# motherboard_v3.net
KiCad netlist of a schematic drawn in EAGLE
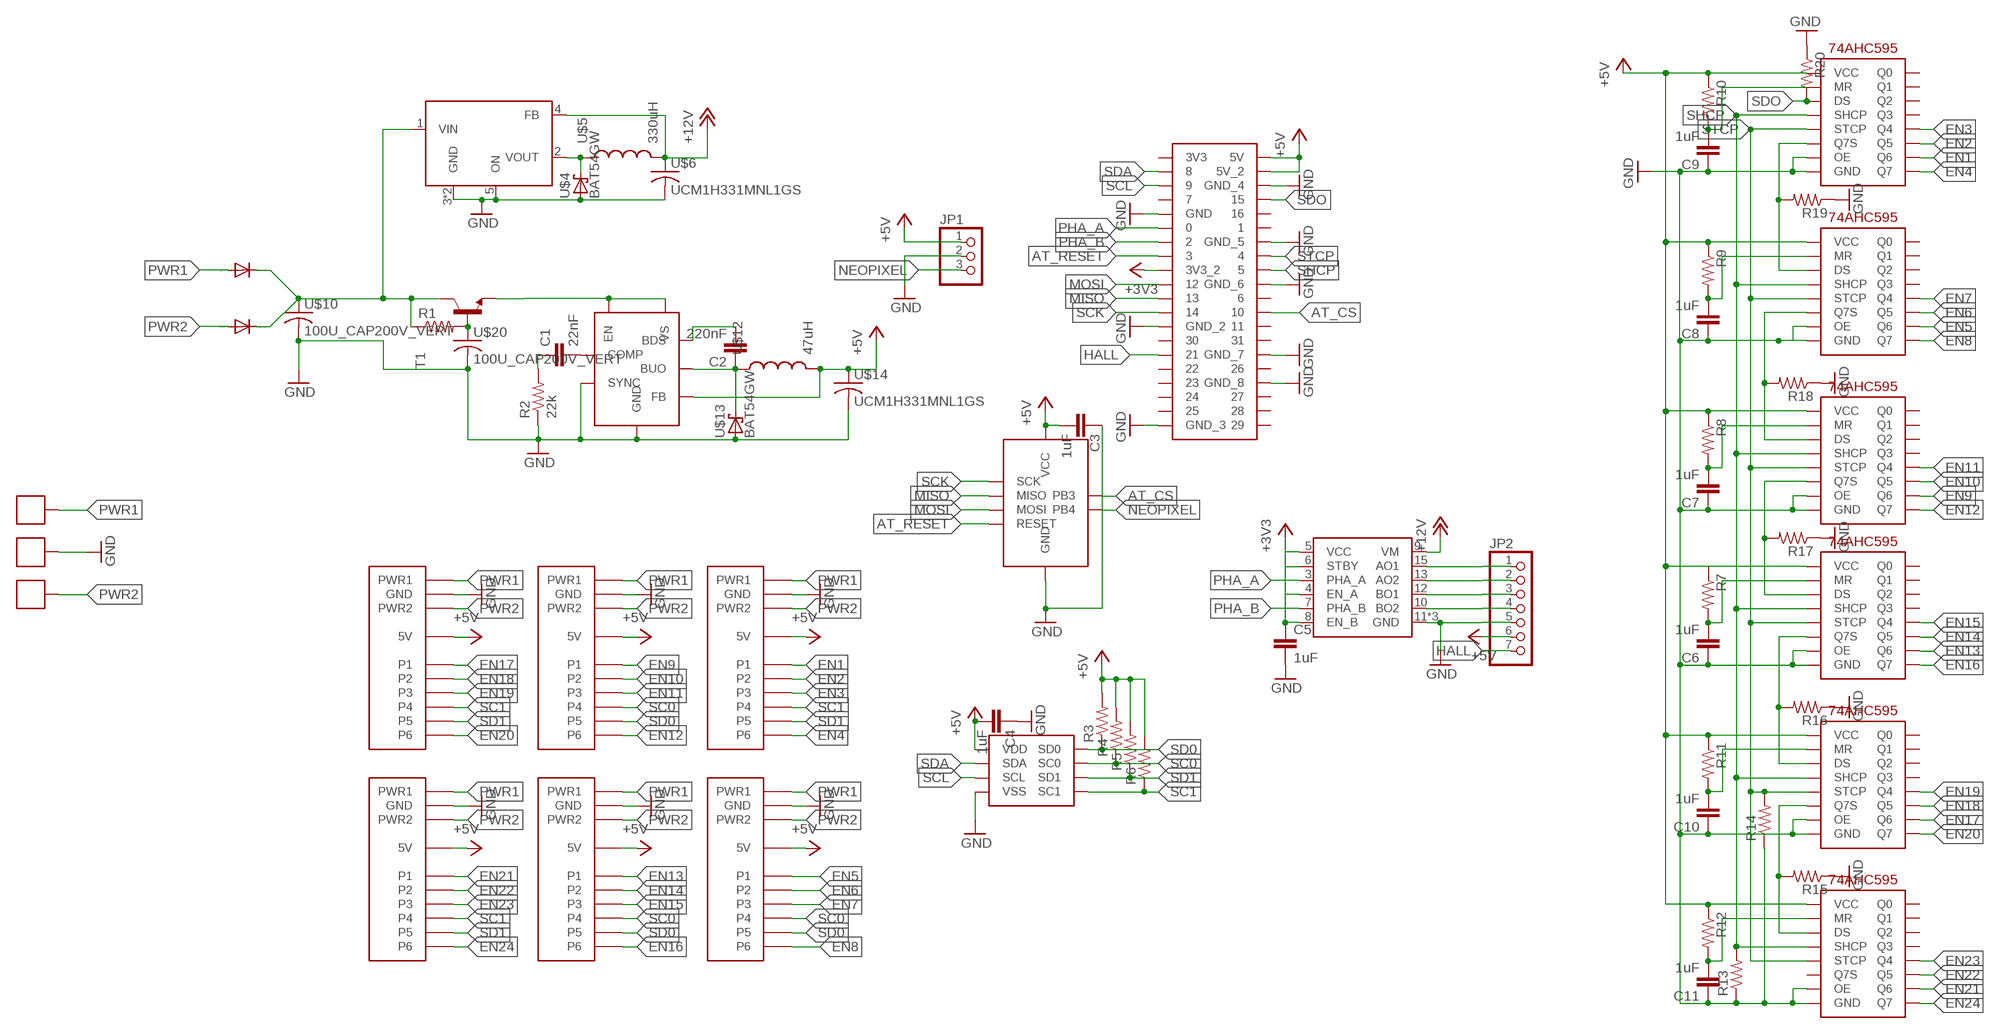
[diagram p0: schematic, sheet 1]

(export (version "E")
  (design (tool "Eeschema 10.0.6"))
  (components
    (comp (ref "B1")
      (value "PCIE_SOCKET")
      (footprint "eagle-import:PCIE_SOCKET")
      (libsource (lib "eagle-import") (part "PCIE_SOCKET"))
    )
    (comp (ref "B2")
      (value "PCIE_SOCKET")
      (footprint "eagle-import:PCIE_SOCKET")
      (libsource (lib "eagle-import") (part "PCIE_SOCKET"))
    )
    (comp (ref "B3")
      (value "PCIE_SOCKET")
      (footprint "eagle-import:PCIE_SOCKET")
      (libsource (lib "eagle-import") (part "PCIE_SOCKET"))
    )
    (comp (ref "B4")
      (value "PCIE_SOCKET")
      (footprint "eagle-import:PCIE_SOCKET")
      (libsource (lib "eagle-import") (part "PCIE_SOCKET"))
    )
    (comp (ref "B5")
      (value "PCIE_SOCKET")
      (footprint "eagle-import:PCIE_SOCKET")
      (libsource (lib "eagle-import") (part "PCIE_SOCKET"))
    )
    (comp (ref "B6")
      (value "PCIE_SOCKET")
      (footprint "eagle-import:PCIE_SOCKET")
      (libsource (lib "eagle-import") (part "PCIE_SOCKET"))
    )
    (comp (ref "C1")
      (value "22nF")
      (footprint "eagle-import:C0805")
      (libsource (lib "eagle-import") (part "C-EUC0805"))
    )
    (comp (ref "C2")
      (value "220nF")
      (footprint "eagle-import:C0805")
      (libsource (lib "eagle-import") (part "C-EUC0805"))
    )
    (comp (ref "C3")
      (value "1uF")
      (footprint "eagle-import:C0805")
      (libsource (lib "eagle-import") (part "C-EUC0805"))
    )
    (comp (ref "C4")
      (value "1uF")
      (footprint "eagle-import:C0805")
      (libsource (lib "eagle-import") (part "C-EUC0805"))
    )
    (comp (ref "C5")
      (value "1uF")
      (footprint "eagle-import:C0805")
      (libsource (lib "eagle-import") (part "C-EUC0805"))
    )
    (comp (ref "C6")
      (value "1uF")
      (footprint "eagle-import:C0805")
      (libsource (lib "eagle-import") (part "C-EUC0805"))
    )
    (comp (ref "C7")
      (value "1uF")
      (footprint "eagle-import:C0805")
      (libsource (lib "eagle-import") (part "C-EUC0805"))
    )
    (comp (ref "C8")
      (value "1uF")
      (footprint "eagle-import:C0805")
      (libsource (lib "eagle-import") (part "C-EUC0805"))
    )
    (comp (ref "C9")
      (value "1uF")
      (footprint "eagle-import:C0805")
      (libsource (lib "eagle-import") (part "C-EUC0805"))
    )
    (comp (ref "C10")
      (value "1uF")
      (footprint "eagle-import:C0805")
      (libsource (lib "eagle-import") (part "C-EUC0805"))
    )
    (comp (ref "C11")
      (value "1uF")
      (footprint "eagle-import:C0805")
      (libsource (lib "eagle-import") (part "C-EUC0805"))
    )
    (comp (ref "JP1")
      (value "PINHD-1X3")
      (footprint "eagle-import:1X03")
      (libsource (lib "eagle-import") (part "PINHD-1X3"))
    )
    (comp (ref "JP2")
      (value "PINHD-1X7")
      (footprint "eagle-import:1X07")
      (libsource (lib "eagle-import") (part "PINHD-1X7"))
    )
    (comp (ref "R1")
      (value "R-US_R1206")
      (footprint "eagle-import:R1206")
      (libsource (lib "eagle-import") (part "R-US_R1206"))
    )
    (comp (ref "R2")
      (value "22k")
      (footprint "eagle-import:R1206")
      (libsource (lib "eagle-import") (part "R-US_R1206"))
    )
    (comp (ref "R3")
      (value "R-US_R0805")
      (footprint "eagle-import:R0805")
      (libsource (lib "eagle-import") (part "R-US_R0805"))
    )
    (comp (ref "R4")
      (value "R-US_R0805")
      (footprint "eagle-import:R0805")
      (libsource (lib "eagle-import") (part "R-US_R0805"))
    )
    (comp (ref "R5")
      (value "R-US_R0805")
      (footprint "eagle-import:R0805")
      (libsource (lib "eagle-import") (part "R-US_R0805"))
    )
    (comp (ref "R6")
      (value "R-US_R0805")
      (footprint "eagle-import:R0805")
      (libsource (lib "eagle-import") (part "R-US_R0805"))
    )
    (comp (ref "R7")
      (value "R-US_R0805")
      (footprint "eagle-import:R0805")
      (libsource (lib "eagle-import") (part "R-US_R0805"))
    )
    (comp (ref "R8")
      (value "R-US_R0805")
      (footprint "eagle-import:R0805")
      (libsource (lib "eagle-import") (part "R-US_R0805"))
    )
    (comp (ref "R9")
      (value "R-US_R0805")
      (footprint "eagle-import:R0805")
      (libsource (lib "eagle-import") (part "R-US_R0805"))
    )
    (comp (ref "R10")
      (value "R-US_R0805")
      (footprint "eagle-import:R0805")
      (libsource (lib "eagle-import") (part "R-US_R0805"))
    )
    (comp (ref "R11")
      (value "R-US_R0805")
      (footprint "eagle-import:R0805")
      (libsource (lib "eagle-import") (part "R-US_R0805"))
    )
    (comp (ref "R12")
      (value "R-US_R0805")
      (footprint "eagle-import:R0805")
      (libsource (lib "eagle-import") (part "R-US_R0805"))
    )
    (comp (ref "R13")
      (value "R-US_R0805")
      (footprint "eagle-import:R0805")
      (libsource (lib "eagle-import") (part "R-US_R0805"))
    )
    (comp (ref "R14")
      (value "R-US_R0805")
      (footprint "eagle-import:R0805")
      (libsource (lib "eagle-import") (part "R-US_R0805"))
    )
    (comp (ref "R15")
      (value "R-US_R0805")
      (footprint "eagle-import:R0805")
      (libsource (lib "eagle-import") (part "R-US_R0805"))
    )
    (comp (ref "R16")
      (value "R-US_R0805")
      (footprint "eagle-import:R0805")
      (libsource (lib "eagle-import") (part "R-US_R0805"))
    )
    (comp (ref "R17")
      (value "R-US_R0805")
      (footprint "eagle-import:R0805")
      (libsource (lib "eagle-import") (part "R-US_R0805"))
    )
    (comp (ref "R18")
      (value "R-US_R0805")
      (footprint "eagle-import:R0805")
      (libsource (lib "eagle-import") (part "R-US_R0805"))
    )
    (comp (ref "R19")
      (value "R-US_R0805")
      (footprint "eagle-import:R0805")
      (libsource (lib "eagle-import") (part "R-US_R0805"))
    )
    (comp (ref "R20")
      (value "R-US_R0805")
      (footprint "eagle-import:R0805")
      (libsource (lib "eagle-import") (part "R-US_R0805"))
    )
    (comp (ref "T1")
      (value "-NPN-SOT23-EBC")
      (footprint "eagle-import:SOT23-EBC")
      (libsource (lib "eagle-import") (part "-NPN-SOT23-EBC"))
    )
    (comp (ref "U$1")
      (value "RPI_SOCKET")
      (footprint "eagle-import:40PIN_SOCKET")
      (libsource (lib "eagle-import") (part "RPI_SOCKET"))
    )
    (comp (ref "U$2")
      (value "TC78H620FNG")
      (footprint "eagle-import:SSOP16")
      (libsource (lib "eagle-import") (part "TC78H620FNG"))
    )
    (comp (ref "U$3")
      (value "TL2575HV-12IKTTR")
      (footprint "eagle-import:TO170P1524X483-6")
      (libsource (lib "eagle-import") (part "TL2575HV-12IKTTR"))
    )
    (comp (ref "U$4")
      (value "BAT54GW")
      (footprint "eagle-import:SOD3616X130")
      (libsource (lib "eagle-import") (part "BAT54GW"))
    )
    (comp (ref "U$5")
      (value "330uH")
      (footprint "eagle-import:SRN8040TA")
      (libsource (lib "eagle-import") (part "SRN8040TA"))
    )
    (comp (ref "U$6")
      (value "UCM1H331MNL1GS")
      (footprint "eagle-import:CAPAE1030X1050")
      (libsource (lib "eagle-import") (part "UCM1H331MNL1GS"))
    )
    (comp (ref "U$7")
      (value "74HC595_QFN")
      (footprint "eagle-import:QFN50P250X350X100-16")
      (libsource (lib "eagle-import") (part "74HC595_QFN"))
    )
    (comp (ref "U$8")
      (value "BAS16GW")
      (footprint "eagle-import:SOD3616X130")
      (libsource (lib "eagle-import") (part "BAS16GW"))
    )
    (comp (ref "U$9")
      (value "BAS16GW")
      (footprint "eagle-import:SOD3616X130")
      (libsource (lib "eagle-import") (part "BAS16GW"))
    )
    (comp (ref "U$10")
      (value "100U_CAP200V_VERT")
      (footprint "eagle-import:VERT_CAP")
      (libsource (lib "eagle-import") (part "100U_CAP200V_VERT"))
    )
    (comp (ref "U$11")
      (value "ATTINY85")
      (footprint "eagle-import:SOIC127P599X175-8")
      (libsource (lib "eagle-import") (part "ATTINY85"))
    )
    (comp (ref "U$12")
      (value "47uH")
      (footprint "eagle-import:SRN8040TA")
      (libsource (lib "eagle-import") (part "SRN8040TA"))
    )
    (comp (ref "U$13")
      (value "BAT54GW")
      (footprint "eagle-import:SOD3616X130")
      (libsource (lib "eagle-import") (part "BAT54GW"))
    )
    (comp (ref "U$14")
      (value "UCM1H331MNL1GS")
      (footprint "eagle-import:CAPAE1030X1050")
      (libsource (lib "eagle-import") (part "UCM1H331MNL1GS"))
    )
    (comp (ref "U$17")
      (value "1935310")
      (footprint "eagle-import:1935310")
      (libsource (lib "eagle-import") (part "1935310"))
    )
    (comp (ref "U$18")
      (value "1935310")
      (footprint "eagle-import:1935310")
      (libsource (lib "eagle-import") (part "1935310"))
    )
    (comp (ref "U$19")
      (value "1935310")
      (footprint "eagle-import:1935310")
      (libsource (lib "eagle-import") (part "1935310"))
    )
    (comp (ref "U$20")
      (value "100U_CAP200V_VERT")
      (footprint "eagle-import:VERT_CAP")
      (libsource (lib "eagle-import") (part "100U_CAP200V_VERT"))
    )
    (comp (ref "U$21")
      (value "PCA9540BDP")
      (footprint "eagle-import:TSSOP8")
      (libsource (lib "eagle-import") (part "PCA9540BDP"))
    )
    (comp (ref "U$22")
      (value "74HC595_QFN")
      (footprint "eagle-import:QFN50P250X350X100-16")
      (libsource (lib "eagle-import") (part "74HC595_QFN"))
    )
    (comp (ref "U$23")
      (value "74HC595_QFN")
      (footprint "eagle-import:QFN50P250X350X100-16")
      (libsource (lib "eagle-import") (part "74HC595_QFN"))
    )
    (comp (ref "U$24")
      (value "74HC595_QFN")
      (footprint "eagle-import:QFN50P250X350X100-16")
      (libsource (lib "eagle-import") (part "74HC595_QFN"))
    )
    (comp (ref "U$25")
      (value "74HC595_QFN")
      (footprint "eagle-import:QFN50P250X350X100-16")
      (libsource (lib "eagle-import") (part "74HC595_QFN"))
    )
    (comp (ref "U$26")
      (value "74HC595_QFN")
      (footprint "eagle-import:QFN50P250X350X100-16")
      (libsource (lib "eagle-import") (part "74HC595_QFN"))
    )
    (comp (ref "U1")
      (value "IFX91041EJV50XUMA1")
      (footprint "eagle-import:SOIC127P600X170-8")
      (libsource (lib "eagle-import") (part "IFX91041EJV50XUMA1"))
    )
  )
  (nets
    (net (code "1") (name "+3V3") (class "Default")
      (node (ref "C5") (pin "1") (pinfunction "1_1") (pintype "passive"))
      (node (ref "U$1") (pin "P17") (pinfunction "3V3_2_P17") (pintype "bidirectional"))
      (node (ref "U$2") (pin "4") (pinfunction "EN_A_4") (pintype "bidirectional"))
      (node (ref "U$2") (pin "5") (pinfunction "VCC_5") (pintype "bidirectional"))
      (node (ref "U$2") (pin "6") (pinfunction "STBY_6") (pintype "bidirectional"))
      (node (ref "U$2") (pin "8") (pinfunction "EN_B_8") (pintype "bidirectional"))
    )
    (net (code "2") (name "+5V") (class "Default")
      (node (ref "B1") (pin "5V_1") (pinfunction "5V_5V_1") (pintype "passive"))
      (node (ref "B1") (pin "5V_2") (pinfunction "5V_5V_2") (pintype "passive"))
      (node (ref "B2") (pin "5V_1") (pinfunction "5V_5V_1") (pintype "passive"))
      (node (ref "B2") (pin "5V_2") (pinfunction "5V_5V_2") (pintype "passive"))
      (node (ref "B3") (pin "5V_1") (pinfunction "5V_5V_1") (pintype "passive"))
      (node (ref "B3") (pin "5V_2") (pinfunction "5V_5V_2") (pintype "passive"))
      (node (ref "B4") (pin "5V_1") (pinfunction "5V_5V_1") (pintype "passive"))
      (node (ref "B4") (pin "5V_2") (pinfunction "5V_5V_2") (pintype "passive"))
      (node (ref "B5") (pin "5V_1") (pinfunction "5V_5V_1") (pintype "passive"))
      (node (ref "B5") (pin "5V_2") (pinfunction "5V_5V_2") (pintype "passive"))
      (node (ref "B6") (pin "5V_1") (pinfunction "5V_5V_1") (pintype "passive"))
      (node (ref "B6") (pin "5V_2") (pinfunction "5V_5V_2") (pintype "passive"))
      (node (ref "C3") (pin "2") (pinfunction "2_2") (pintype "passive"))
      (node (ref "C4") (pin "2") (pinfunction "2_2") (pintype "passive"))
      (node (ref "JP1") (pin "1") (pinfunction "1_1") (pintype "passive"))
      (node (ref "JP2") (pin "6") (pinfunction "6_6") (pintype "passive"))
      (node (ref "R10") (pin "1") (pinfunction "1_1") (pintype "passive"))
      (node (ref "R11") (pin "1") (pinfunction "1_1") (pintype "passive"))
      (node (ref "R12") (pin "1") (pinfunction "1_1") (pintype "passive"))
      (node (ref "R3") (pin "2") (pinfunction "2_2") (pintype "passive"))
      (node (ref "R4") (pin "2") (pinfunction "2_2") (pintype "passive"))
      (node (ref "R5") (pin "2") (pinfunction "2_2") (pintype "passive"))
      (node (ref "R6") (pin "2") (pinfunction "2_2") (pintype "passive"))
      (node (ref "R7") (pin "1") (pinfunction "1_1") (pintype "passive"))
      (node (ref "R8") (pin "1") (pinfunction "1_1") (pintype "passive"))
      (node (ref "R9") (pin "1") (pinfunction "1_1") (pintype "passive"))
      (node (ref "U$1") (pin "P2") (pinfunction "5V_P2") (pintype "bidirectional"))
      (node (ref "U$1") (pin "P4") (pinfunction "5V_2_P4") (pintype "bidirectional"))
      (node (ref "U$11") (pin "8") (pinfunction "VCC_8") (pintype "bidirectional"))
      (node (ref "U$12") (pin "P$2") (pinfunction "2_P$2") (pintype "passive"))
      (node (ref "U$14") (pin "1") (pinfunction "1_1") (pintype "passive"))
      (node (ref "U$21") (pin "3") (pinfunction "VDD_3") (pintype "bidirectional"))
      (node (ref "U$22") (pin "P16") (pinfunction "VCC_P16") (pintype "bidirectional"))
      (node (ref "U$23") (pin "P16") (pinfunction "VCC_P16") (pintype "bidirectional"))
      (node (ref "U$24") (pin "P16") (pinfunction "VCC_P16") (pintype "bidirectional"))
      (node (ref "U$25") (pin "P16") (pinfunction "VCC_P16") (pintype "bidirectional"))
      (node (ref "U$26") (pin "P16") (pinfunction "VCC_P16") (pintype "bidirectional"))
      (node (ref "U$7") (pin "P16") (pinfunction "VCC_P16") (pintype "bidirectional"))
      (node (ref "U1") (pin "4") (pinfunction "FB_4") (pintype "bidirectional"))
    )
    (net (code "3") (name "+12V") (class "Default")
      (node (ref "U$2") (pin "9") (pinfunction "VM_9") (pintype "bidirectional"))
      (node (ref "U$3") (pin "4") (pinfunction "FB_4") (pintype "bidirectional"))
      (node (ref "U$5") (pin "P$2") (pinfunction "2_P$2") (pintype "passive"))
      (node (ref "U$6") (pin "1") (pinfunction "1_1") (pintype "passive"))
    )
    (net (code "4") (name "AT_CS") (class "Default")
      (node (ref "U$1") (pin "P24") (pinfunction "10_P24") (pintype "bidirectional"))
      (node (ref "U$11") (pin "2") (pinfunction "PB3_2") (pintype "bidirectional"))
    )
    (net (code "5") (name "AT_RESET") (class "Default")
      (node (ref "U$1") (pin "P15") (pinfunction "3_P15") (pintype "bidirectional"))
      (node (ref "U$11") (pin "1") (pinfunction "RESET_1") (pintype "bidirectional"))
    )
    (net (code "6") (name "EN1") (class "Default")
      (node (ref "B1") (pin "P1") (pinfunction "P1_P1") (pintype "bidirectional"))
      (node (ref "U$7") (pin "P6") (pinfunction "Q6_P6") (pintype "bidirectional"))
    )
    (net (code "7") (name "EN2") (class "Default")
      (node (ref "B1") (pin "P2") (pinfunction "P2_P2") (pintype "bidirectional"))
      (node (ref "U$7") (pin "P5") (pinfunction "Q5_P5") (pintype "bidirectional"))
    )
    (net (code "8") (name "EN3") (class "Default")
      (node (ref "B1") (pin "P3") (pinfunction "P3_P3") (pintype "bidirectional"))
      (node (ref "U$7") (pin "P4") (pinfunction "Q4_P4") (pintype "bidirectional"))
    )
    (net (code "9") (name "EN4") (class "Default")
      (node (ref "B1") (pin "P6") (pinfunction "P6_P6") (pintype "bidirectional"))
      (node (ref "U$7") (pin "P7") (pinfunction "Q7_P7") (pintype "bidirectional"))
    )
    (net (code "10") (name "EN5") (class "Default")
      (node (ref "B2") (pin "P1") (pinfunction "P1_P1") (pintype "bidirectional"))
      (node (ref "U$22") (pin "P6") (pinfunction "Q6_P6") (pintype "bidirectional"))
    )
    (net (code "11") (name "EN6") (class "Default")
      (node (ref "B2") (pin "P2") (pinfunction "P2_P2") (pintype "bidirectional"))
      (node (ref "U$22") (pin "P5") (pinfunction "Q5_P5") (pintype "bidirectional"))
    )
    (net (code "12") (name "EN7") (class "Default")
      (node (ref "B2") (pin "P3") (pinfunction "P3_P3") (pintype "bidirectional"))
      (node (ref "U$22") (pin "P4") (pinfunction "Q4_P4") (pintype "bidirectional"))
    )
    (net (code "13") (name "EN8") (class "Default")
      (node (ref "B2") (pin "P6") (pinfunction "P6_P6") (pintype "bidirectional"))
      (node (ref "U$22") (pin "P7") (pinfunction "Q7_P7") (pintype "bidirectional"))
    )
    (net (code "14") (name "EN9") (class "Default")
      (node (ref "B3") (pin "P1") (pinfunction "P1_P1") (pintype "bidirectional"))
      (node (ref "U$23") (pin "P6") (pinfunction "Q6_P6") (pintype "bidirectional"))
    )
    (net (code "15") (name "EN10") (class "Default")
      (node (ref "B3") (pin "P2") (pinfunction "P2_P2") (pintype "bidirectional"))
      (node (ref "U$23") (pin "P5") (pinfunction "Q5_P5") (pintype "bidirectional"))
    )
    (net (code "16") (name "EN11") (class "Default")
      (node (ref "B3") (pin "P3") (pinfunction "P3_P3") (pintype "bidirectional"))
      (node (ref "U$23") (pin "P4") (pinfunction "Q4_P4") (pintype "bidirectional"))
    )
    (net (code "17") (name "EN12") (class "Default")
      (node (ref "B3") (pin "P6") (pinfunction "P6_P6") (pintype "bidirectional"))
      (node (ref "U$23") (pin "P7") (pinfunction "Q7_P7") (pintype "bidirectional"))
    )
    (net (code "18") (name "EN13") (class "Default")
      (node (ref "B4") (pin "P1") (pinfunction "P1_P1") (pintype "bidirectional"))
      (node (ref "U$24") (pin "P6") (pinfunction "Q6_P6") (pintype "bidirectional"))
    )
    (net (code "19") (name "EN14") (class "Default")
      (node (ref "B4") (pin "P2") (pinfunction "P2_P2") (pintype "bidirectional"))
      (node (ref "U$24") (pin "P5") (pinfunction "Q5_P5") (pintype "bidirectional"))
    )
    (net (code "20") (name "EN15") (class "Default")
      (node (ref "B4") (pin "P3") (pinfunction "P3_P3") (pintype "bidirectional"))
      (node (ref "U$24") (pin "P4") (pinfunction "Q4_P4") (pintype "bidirectional"))
    )
    (net (code "21") (name "EN16") (class "Default")
      (node (ref "B4") (pin "P6") (pinfunction "P6_P6") (pintype "bidirectional"))
      (node (ref "U$24") (pin "P7") (pinfunction "Q7_P7") (pintype "bidirectional"))
    )
    (net (code "22") (name "EN17") (class "Default")
      (node (ref "B5") (pin "P1") (pinfunction "P1_P1") (pintype "bidirectional"))
      (node (ref "U$25") (pin "P6") (pinfunction "Q6_P6") (pintype "bidirectional"))
    )
    (net (code "23") (name "EN18") (class "Default")
      (node (ref "B5") (pin "P2") (pinfunction "P2_P2") (pintype "bidirectional"))
      (node (ref "U$25") (pin "P5") (pinfunction "Q5_P5") (pintype "bidirectional"))
    )
    (net (code "24") (name "EN19") (class "Default")
      (node (ref "B5") (pin "P3") (pinfunction "P3_P3") (pintype "bidirectional"))
      (node (ref "U$25") (pin "P4") (pinfunction "Q4_P4") (pintype "bidirectional"))
    )
    (net (code "25") (name "EN20") (class "Default")
      (node (ref "B5") (pin "P6") (pinfunction "P6_P6") (pintype "bidirectional"))
      (node (ref "U$25") (pin "P7") (pinfunction "Q7_P7") (pintype "bidirectional"))
    )
    (net (code "26") (name "EN21") (class "Default")
      (node (ref "B6") (pin "P1") (pinfunction "P1_P1") (pintype "bidirectional"))
      (node (ref "U$26") (pin "P6") (pinfunction "Q6_P6") (pintype "bidirectional"))
    )
    (net (code "27") (name "EN22") (class "Default")
      (node (ref "B6") (pin "P2") (pinfunction "P2_P2") (pintype "bidirectional"))
      (node (ref "U$26") (pin "P5") (pinfunction "Q5_P5") (pintype "bidirectional"))
    )
    (net (code "28") (name "EN23") (class "Default")
      (node (ref "B6") (pin "P3") (pinfunction "P3_P3") (pintype "bidirectional"))
      (node (ref "U$26") (pin "P4") (pinfunction "Q4_P4") (pintype "bidirectional"))
    )
    (net (code "29") (name "EN24") (class "Default")
      (node (ref "B6") (pin "P6") (pinfunction "P6_P6") (pintype "bidirectional"))
      (node (ref "U$26") (pin "P7") (pinfunction "Q7_P7") (pintype "bidirectional"))
    )
    (net (code "30") (name "GND") (class "Default")
      (node (ref "B1") (pin "GND1") (pinfunction "GND_GND1") (pintype "passive"))
      (node (ref "B1") (pin "GND2") (pinfunction "GND_GND2") (pintype "passive"))
      (node (ref "B2") (pin "GND1") (pinfunction "GND_GND1") (pintype "passive"))
      (node (ref "B2") (pin "GND2") (pinfunction "GND_GND2") (pintype "passive"))
      (node (ref "B3") (pin "GND1") (pinfunction "GND_GND1") (pintype "passive"))
      (node (ref "B3") (pin "GND2") (pinfunction "GND_GND2") (pintype "passive"))
      (node (ref "B4") (pin "GND1") (pinfunction "GND_GND1") (pintype "passive"))
      (node (ref "B4") (pin "GND2") (pinfunction "GND_GND2") (pintype "passive"))
      (node (ref "B5") (pin "GND1") (pinfunction "GND_GND1") (pintype "passive"))
      (node (ref "B5") (pin "GND2") (pinfunction "GND_GND2") (pintype "passive"))
      (node (ref "B6") (pin "GND1") (pinfunction "GND_GND1") (pintype "passive"))
      (node (ref "B6") (pin "GND2") (pinfunction "GND_GND2") (pintype "passive"))
      (node (ref "C10") (pin "1") (pinfunction "1_1") (pintype "passive"))
      (node (ref "C11") (pin "1") (pinfunction "1_1") (pintype "passive"))
      (node (ref "C3") (pin "1") (pinfunction "1_1") (pintype "passive"))
      (node (ref "C4") (pin "1") (pinfunction "1_1") (pintype "passive"))
      (node (ref "C5") (pin "2") (pinfunction "2_2") (pintype "passive"))
      (node (ref "C6") (pin "1") (pinfunction "1_1") (pintype "passive"))
      (node (ref "C7") (pin "1") (pinfunction "1_1") (pintype "passive"))
      (node (ref "C8") (pin "1") (pinfunction "1_1") (pintype "passive"))
      (node (ref "C9") (pin "1") (pinfunction "1_1") (pintype "passive"))
      (node (ref "JP1") (pin "2") (pinfunction "2_2") (pintype "passive"))
      (node (ref "JP2") (pin "5") (pinfunction "5_5") (pintype "passive"))
      (node (ref "R13") (pin "1") (pinfunction "1_1") (pintype "passive"))
      (node (ref "R14") (pin "1") (pinfunction "1_1") (pintype "passive"))
      (node (ref "R15") (pin "1") (pinfunction "1_1") (pintype "passive"))
      (node (ref "R16") (pin "1") (pinfunction "1_1") (pintype "passive"))
      (node (ref "R17") (pin "1") (pinfunction "1_1") (pintype "passive"))
      (node (ref "R18") (pin "1") (pinfunction "1_1") (pintype "passive"))
      (node (ref "R19") (pin "1") (pinfunction "1_1") (pintype "passive"))
      (node (ref "R2") (pin "1") (pinfunction "1_1") (pintype "passive"))
      (node (ref "R20") (pin "1") (pinfunction "1_1") (pintype "passive"))
      (node (ref "U$1") (pin "P14") (pinfunction "GND_5_P14") (pintype "bidirectional"))
      (node (ref "U$1") (pin "P20") (pinfunction "GND_6_P20") (pintype "bidirectional"))
      (node (ref "U$1") (pin "P25") (pinfunction "GND_2_P25") (pintype "bidirectional"))
      (node (ref "U$1") (pin "P30") (pinfunction "GND_7_P30") (pintype "bidirectional"))
      (node (ref "U$1") (pin "P34") (pinfunction "GND_8_P34") (pintype "bidirectional"))
      (node (ref "U$1") (pin "P39") (pinfunction "GND_3_P39") (pintype "bidirectional"))
      (node (ref "U$1") (pin "P6") (pinfunction "GND_4_P6") (pintype "bidirectional"))
      (node (ref "U$1") (pin "P9") (pinfunction "GND_P9") (pintype "bidirectional"))
      (node (ref "U$10") (pin "P$4") (pinfunction "2_P$4") (pintype "passive"))
      (node (ref "U$11") (pin "4") (pinfunction "GND_4") (pintype "bidirectional"))
      (node (ref "U$13") (pin "2") (pinfunction "A_2") (pintype "passive"))
      (node (ref "U$14") (pin "2") (pinfunction "2_2") (pintype "passive"))
      (node (ref "U$18") (pin "P$1") (pinfunction "P$1_P$1") (pintype "bidirectional"))
      (node (ref "U$18") (pin "P$2") (pinfunction "P$1_P$2") (pintype "bidirectional"))
      (node (ref "U$2") (pin "11") (pinfunction "GND_11") (pintype "bidirectional"))
      (node (ref "U$2") (pin "14") (pinfunction "GND_14") (pintype "bidirectional"))
      (node (ref "U$2") (pin "16") (pinfunction "GND_16") (pintype "bidirectional"))
      (node (ref "U$20") (pin "P$4") (pinfunction "2_P$4") (pintype "passive"))
      (node (ref "U$21") (pin "6") (pinfunction "VSS_6") (pintype "bidirectional"))
      (node (ref "U$22") (pin "P$1") (pinfunction "GND_P$1") (pintype "bidirectional"))
      (node (ref "U$22") (pin "P13") (pinfunction "OE_P13") (pintype "bidirectional"))
      (node (ref "U$22") (pin "P8") (pinfunction "GND_P8") (pintype "bidirectional"))
      (node (ref "U$23") (pin "P$1") (pinfunction "GND_P$1") (pintype "bidirectional"))
      (node (ref "U$23") (pin "P13") (pinfunction "OE_P13") (pintype "bidirectional"))
      (node (ref "U$23") (pin "P8") (pinfunction "GND_P8") (pintype "bidirectional"))
      (node (ref "U$24") (pin "P$1") (pinfunction "GND_P$1") (pintype "bidirectional"))
      (node (ref "U$24") (pin "P13") (pinfunction "OE_P13") (pintype "bidirectional"))
      (node (ref "U$24") (pin "P8") (pinfunction "GND_P8") (pintype "bidirectional"))
      (node (ref "U$25") (pin "P$1") (pinfunction "GND_P$1") (pintype "bidirectional"))
      (node (ref "U$25") (pin "P13") (pinfunction "OE_P13") (pintype "bidirectional"))
      (node (ref "U$25") (pin "P8") (pinfunction "GND_P8") (pintype "bidirectional"))
      (node (ref "U$26") (pin "P$1") (pinfunction "GND_P$1") (pintype "bidirectional"))
      (node (ref "U$26") (pin "P13") (pinfunction "OE_P13") (pintype "bidirectional"))
      (node (ref "U$26") (pin "P8") (pinfunction "GND_P8") (pintype "bidirectional"))
      (node (ref "U$3") (pin "3") (pinfunction "GND_3") (pintype "bidirectional"))
      (node (ref "U$3") (pin "5") (pinfunction "ON_5") (pintype "bidirectional"))
      (node (ref "U$3") (pin "6") (pinfunction "GND_6") (pintype "bidirectional"))
      (node (ref "U$4") (pin "2") (pinfunction "A_2") (pintype "passive"))
      (node (ref "U$6") (pin "2") (pinfunction "2_2") (pintype "passive"))
      (node (ref "U$7") (pin "P$1") (pinfunction "GND_P$1") (pintype "bidirectional"))
      (node (ref "U$7") (pin "P13") (pinfunction "OE_P13") (pintype "bidirectional"))
      (node (ref "U$7") (pin "P8") (pinfunction "GND_P8") (pintype "bidirectional"))
      (node (ref "U1") (pin "1") (pinfunction "SYNC_1") (pintype "bidirectional"))
      (node (ref "U1") (pin "2") (pinfunction "GND_2") (pintype "bidirectional"))
      (node (ref "U1") (pin "PAD") (pinfunction "GND_PAD") (pintype "bidirectional"))
    )
    (net (code "31") (name "HALL") (class "Default")
      (node (ref "JP2") (pin "7") (pinfunction "7_7") (pintype "passive"))
      (node (ref "U$1") (pin "P29") (pinfunction "21_P29") (pintype "bidirectional"))
    )
    (net (code "32") (name "MISO") (class "Default")
      (node (ref "U$1") (pin "P21") (pinfunction "13_P21") (pintype "bidirectional"))
      (node (ref "U$11") (pin "6") (pinfunction "MISO_6") (pintype "bidirectional"))
    )
    (net (code "33") (name "MOSI") (class "Default")
      (node (ref "U$1") (pin "P19") (pinfunction "12_P19") (pintype "bidirectional"))
      (node (ref "U$11") (pin "5") (pinfunction "MOSI_5") (pintype "bidirectional"))
    )
    (net (code "34") (name "NEOPIXEL") (class "Default")
      (node (ref "JP1") (pin "3") (pinfunction "3_3") (pintype "passive"))
      (node (ref "U$11") (pin "3") (pinfunction "PB4_3") (pintype "bidirectional"))
    )
    (net (code "35") (name "Net-(C1-Pad1)") (class "Default")
      (node (ref "C1") (pin "1") (pinfunction "1_1") (pintype "passive"))
      (node (ref "R2") (pin "2") (pinfunction "2_2") (pintype "passive"))
    )
    (net (code "36") (name "Net-(U$2-AO1)") (class "Default")
      (node (ref "JP2") (pin "1") (pinfunction "1_1") (pintype "passive"))
      (node (ref "U$2") (pin "15") (pinfunction "AO1_15") (pintype "bidirectional"))
    )
    (net (code "37") (name "Net-(U$2-AO2)") (class "Default")
      (node (ref "JP2") (pin "2") (pinfunction "2_2") (pintype "passive"))
      (node (ref "U$2") (pin "13") (pinfunction "AO2_13") (pintype "bidirectional"))
    )
    (net (code "38") (name "Net-(U$2-BO1)") (class "Default")
      (node (ref "JP2") (pin "3") (pinfunction "3_3") (pintype "passive"))
      (node (ref "U$2") (pin "12") (pinfunction "BO1_12") (pintype "bidirectional"))
    )
    (net (code "39") (name "Net-(U$2-BO2)") (class "Default")
      (node (ref "JP2") (pin "4") (pinfunction "4_4") (pintype "passive"))
      (node (ref "U$2") (pin "10") (pinfunction "BO2_10") (pintype "bidirectional"))
    )
    (net (code "40") (name "Net-(U$3-VOUT)") (class "Default")
      (node (ref "U$3") (pin "2") (pinfunction "VOUT_2") (pintype "bidirectional"))
      (node (ref "U$4") (pin "1") (pinfunction "C_1") (pintype "passive"))
      (node (ref "U$5") (pin "P$1") (pinfunction "1_P$1") (pintype "passive"))
    )
    (net (code "41") (name "Net-(U$7-MR)") (class "Default")
      (node (ref "C9") (pin "2") (pinfunction "2_2") (pintype "passive"))
      (node (ref "R10") (pin "2") (pinfunction "2_2") (pintype "passive"))
      (node (ref "U$7") (pin "P10") (pinfunction "MR_P10") (pintype "bidirectional"))
    )
    (net (code "42") (name "Net-(U$10-1)") (class "Default")
      (node (ref "R1") (pin "1") (pinfunction "1_1") (pintype "passive"))
      (node (ref "T1") (pin "C") (pinfunction "C_C") (pintype "passive"))
      (node (ref "U$10") (pin "P$3") (pinfunction "1_P$3") (pintype "passive"))
      (node (ref "U$3") (pin "1") (pinfunction "VIN_1") (pintype "bidirectional"))
      (node (ref "U$8") (pin "1") (pinfunction "C_1") (pintype "passive"))
      (node (ref "U$9") (pin "1") (pinfunction "C_1") (pintype "passive"))
    )
    (net (code "43") (name "Net-(U$12-1)") (class "Default")
      (node (ref "C2") (pin "1") (pinfunction "1_1") (pintype "passive"))
      (node (ref "U$12") (pin "P$1") (pinfunction "1_P$1") (pintype "passive"))
      (node (ref "U$13") (pin "1") (pinfunction "C_1") (pintype "passive"))
      (node (ref "U1") (pin "6") (pinfunction "BUO_6") (pintype "bidirectional"))
    )
    (net (code "44") (name "Net-(U$20-1)") (class "Default")
      (node (ref "R1") (pin "2") (pinfunction "2_2") (pintype "passive"))
      (node (ref "T1") (pin "B") (pinfunction "B_B") (pintype "passive"))
      (node (ref "U$20") (pin "P$3") (pinfunction "1_P$3") (pintype "passive"))
    )
    (net (code "45") (name "Net-(U$22-DS)") (class "Default")
      (node (ref "R19") (pin "2") (pinfunction "2_2") (pintype "passive"))
      (node (ref "U$22") (pin "P14") (pinfunction "DS_P14") (pintype "bidirectional"))
      (node (ref "U$7") (pin "P9") (pinfunction "Q7S_P9") (pintype "bidirectional"))
    )
    (net (code "46") (name "Net-(U$22-MR)") (class "Default")
      (node (ref "C8") (pin "2") (pinfunction "2_2") (pintype "passive"))
      (node (ref "R9") (pin "2") (pinfunction "2_2") (pintype "passive"))
      (node (ref "U$22") (pin "P10") (pinfunction "MR_P10") (pintype "bidirectional"))
    )
    (net (code "47") (name "Net-(U$22-Q7S)") (class "Default")
      (node (ref "R18") (pin "2") (pinfunction "2_2") (pintype "passive"))
      (node (ref "U$22") (pin "P9") (pinfunction "Q7S_P9") (pintype "bidirectional"))
      (node (ref "U$23") (pin "P14") (pinfunction "DS_P14") (pintype "bidirectional"))
    )
    (net (code "48") (name "Net-(U$23-MR)") (class "Default")
      (node (ref "C7") (pin "2") (pinfunction "2_2") (pintype "passive"))
      (node (ref "R8") (pin "2") (pinfunction "2_2") (pintype "passive"))
      (node (ref "U$23") (pin "P10") (pinfunction "MR_P10") (pintype "bidirectional"))
    )
    (net (code "49") (name "Net-(U$23-Q7S)") (class "Default")
      (node (ref "R17") (pin "2") (pinfunction "2_2") (pintype "passive"))
      (node (ref "U$23") (pin "P9") (pinfunction "Q7S_P9") (pintype "bidirectional"))
      (node (ref "U$24") (pin "P14") (pinfunction "DS_P14") (pintype "bidirectional"))
    )
    (net (code "50") (name "Net-(U$24-MR)") (class "Default")
      (node (ref "C6") (pin "2") (pinfunction "2_2") (pintype "passive"))
      (node (ref "R7") (pin "2") (pinfunction "2_2") (pintype "passive"))
      (node (ref "U$24") (pin "P10") (pinfunction "MR_P10") (pintype "bidirectional"))
    )
    (net (code "51") (name "Net-(U$24-Q7S)") (class "Default")
      (node (ref "R16") (pin "2") (pinfunction "2_2") (pintype "passive"))
      (node (ref "U$24") (pin "P9") (pinfunction "Q7S_P9") (pintype "bidirectional"))
      (node (ref "U$25") (pin "P14") (pinfunction "DS_P14") (pintype "bidirectional"))
    )
    (net (code "52") (name "Net-(U$25-MR)") (class "Default")
      (node (ref "C10") (pin "2") (pinfunction "2_2") (pintype "passive"))
      (node (ref "R11") (pin "2") (pinfunction "2_2") (pintype "passive"))
      (node (ref "U$25") (pin "P10") (pinfunction "MR_P10") (pintype "bidirectional"))
    )
    (net (code "53") (name "Net-(U$25-Q7S)") (class "Default")
      (node (ref "R15") (pin "2") (pinfunction "2_2") (pintype "passive"))
      (node (ref "U$25") (pin "P9") (pinfunction "Q7S_P9") (pintype "bidirectional"))
      (node (ref "U$26") (pin "P14") (pinfunction "DS_P14") (pintype "bidirectional"))
    )
    (net (code "54") (name "Net-(U$26-MR)") (class "Default")
      (node (ref "C11") (pin "2") (pinfunction "2_2") (pintype "passive"))
      (node (ref "R12") (pin "2") (pinfunction "2_2") (pintype "passive"))
      (node (ref "U$26") (pin "P10") (pinfunction "MR_P10") (pintype "bidirectional"))
    )
    (net (code "55") (name "Net-(U1-BDS)") (class "Default")
      (node (ref "C2") (pin "2") (pinfunction "2_2") (pintype "passive"))
      (node (ref "U1") (pin "5") (pinfunction "BDS_5") (pintype "bidirectional"))
    )
    (net (code "56") (name "Net-(U1-COMP)") (class "Default")
      (node (ref "C1") (pin "2") (pinfunction "2_2") (pintype "passive"))
      (node (ref "U1") (pin "3") (pinfunction "COMP_3") (pintype "bidirectional"))
    )
    (net (code "57") (name "Net-(U1-EN)") (class "Default")
      (node (ref "T1") (pin "E") (pinfunction "E_E") (pintype "passive"))
      (node (ref "U1") (pin "7") (pinfunction "EN_7") (pintype "bidirectional"))
      (node (ref "U1") (pin "8") (pinfunction "VS_8") (pintype "bidirectional"))
    )
    (net (code "58") (name "PHA_A") (class "Default")
      (node (ref "U$1") (pin "P11") (pinfunction "0_P11") (pintype "bidirectional"))
      (node (ref "U$2") (pin "3") (pinfunction "PHA_A_3") (pintype "bidirectional"))
    )
    (net (code "59") (name "PHA_B") (class "Default")
      (node (ref "U$1") (pin "P13") (pinfunction "2_P13") (pintype "bidirectional"))
      (node (ref "U$2") (pin "7") (pinfunction "PHA_B_7") (pintype "bidirectional"))
    )
    (net (code "60") (name "PWR1") (class "Default")
      (node (ref "B1") (pin "PWR1_1") (pinfunction "PWR1_PWR1_1") (pintype "passive"))
      (node (ref "B1") (pin "PWR1_2") (pinfunction "PWR1_PWR1_2") (pintype "passive"))
      (node (ref "B2") (pin "PWR1_1") (pinfunction "PWR1_PWR1_1") (pintype "passive"))
      (node (ref "B2") (pin "PWR1_2") (pinfunction "PWR1_PWR1_2") (pintype "passive"))
      (node (ref "B3") (pin "PWR1_1") (pinfunction "PWR1_PWR1_1") (pintype "passive"))
      (node (ref "B3") (pin "PWR1_2") (pinfunction "PWR1_PWR1_2") (pintype "passive"))
      (node (ref "B4") (pin "PWR1_1") (pinfunction "PWR1_PWR1_1") (pintype "passive"))
      (node (ref "B4") (pin "PWR1_2") (pinfunction "PWR1_PWR1_2") (pintype "passive"))
      (node (ref "B5") (pin "PWR1_1") (pinfunction "PWR1_PWR1_1") (pintype "passive"))
      (node (ref "B5") (pin "PWR1_2") (pinfunction "PWR1_PWR1_2") (pintype "passive"))
      (node (ref "B6") (pin "PWR1_1") (pinfunction "PWR1_PWR1_1") (pintype "passive"))
      (node (ref "B6") (pin "PWR1_2") (pinfunction "PWR1_PWR1_2") (pintype "passive"))
      (node (ref "U$17") (pin "P$1") (pinfunction "P$1_P$1") (pintype "bidirectional"))
      (node (ref "U$17") (pin "P$2") (pinfunction "P$1_P$2") (pintype "bidirectional"))
      (node (ref "U$8") (pin "2") (pinfunction "A_2") (pintype "passive"))
    )
    (net (code "61") (name "PWR2") (class "Default")
      (node (ref "B1") (pin "PWR2_1") (pinfunction "PWR2_PWR2_1") (pintype "passive"))
      (node (ref "B1") (pin "PWR2_2") (pinfunction "PWR2_PWR2_2") (pintype "passive"))
      (node (ref "B2") (pin "PWR2_1") (pinfunction "PWR2_PWR2_1") (pintype "passive"))
      (node (ref "B2") (pin "PWR2_2") (pinfunction "PWR2_PWR2_2") (pintype "passive"))
      (node (ref "B3") (pin "PWR2_1") (pinfunction "PWR2_PWR2_1") (pintype "passive"))
      (node (ref "B3") (pin "PWR2_2") (pinfunction "PWR2_PWR2_2") (pintype "passive"))
      (node (ref "B4") (pin "PWR2_1") (pinfunction "PWR2_PWR2_1") (pintype "passive"))
      (node (ref "B4") (pin "PWR2_2") (pinfunction "PWR2_PWR2_2") (pintype "passive"))
      (node (ref "B5") (pin "PWR2_1") (pinfunction "PWR2_PWR2_1") (pintype "passive"))
      (node (ref "B5") (pin "PWR2_2") (pinfunction "PWR2_PWR2_2") (pintype "passive"))
      (node (ref "B6") (pin "PWR2_1") (pinfunction "PWR2_PWR2_1") (pintype "passive"))
      (node (ref "B6") (pin "PWR2_2") (pinfunction "PWR2_PWR2_2") (pintype "passive"))
      (node (ref "U$19") (pin "P$1") (pinfunction "P$1_P$1") (pintype "bidirectional"))
      (node (ref "U$19") (pin "P$2") (pinfunction "P$1_P$2") (pintype "bidirectional"))
      (node (ref "U$9") (pin "2") (pinfunction "A_2") (pintype "passive"))
    )
    (net (code "62") (name "SC0") (class "Default")
      (node (ref "B2") (pin "P4") (pinfunction "P4_P4") (pintype "bidirectional"))
      (node (ref "B3") (pin "P4") (pinfunction "P4_P4") (pintype "bidirectional"))
      (node (ref "B4") (pin "P4") (pinfunction "P4_P4") (pintype "bidirectional"))
      (node (ref "R4") (pin "1") (pinfunction "1_1") (pintype "passive"))
      (node (ref "U$21") (pin "5") (pinfunction "SC0_5") (pintype "bidirectional"))
    )
    (net (code "63") (name "SC1") (class "Default")
      (node (ref "B1") (pin "P4") (pinfunction "P4_P4") (pintype "bidirectional"))
      (node (ref "B5") (pin "P4") (pinfunction "P4_P4") (pintype "bidirectional"))
      (node (ref "B6") (pin "P4") (pinfunction "P4_P4") (pintype "bidirectional"))
      (node (ref "R6") (pin "1") (pinfunction "1_1") (pintype "passive"))
      (node (ref "U$21") (pin "8") (pinfunction "SC1_8") (pintype "bidirectional"))
    )
    (net (code "64") (name "SCK") (class "Default")
      (node (ref "U$1") (pin "P23") (pinfunction "14_P23") (pintype "bidirectional"))
      (node (ref "U$11") (pin "7") (pinfunction "SCK_7") (pintype "bidirectional"))
    )
    (net (code "65") (name "SCL") (class "Default")
      (node (ref "U$1") (pin "P5") (pinfunction "9_P5") (pintype "bidirectional"))
      (node (ref "U$21") (pin "1") (pinfunction "SCL_1") (pintype "bidirectional"))
    )
    (net (code "66") (name "SD0") (class "Default")
      (node (ref "B2") (pin "P5") (pinfunction "P5_P5") (pintype "bidirectional"))
      (node (ref "B3") (pin "P5") (pinfunction "P5_P5") (pintype "bidirectional"))
      (node (ref "B4") (pin "P5") (pinfunction "P5_P5") (pintype "bidirectional"))
      (node (ref "R3") (pin "1") (pinfunction "1_1") (pintype "passive"))
      (node (ref "U$21") (pin "4") (pinfunction "SD0_4") (pintype "bidirectional"))
    )
    (net (code "67") (name "SD1") (class "Default")
      (node (ref "B1") (pin "P5") (pinfunction "P5_P5") (pintype "bidirectional"))
      (node (ref "B5") (pin "P5") (pinfunction "P5_P5") (pintype "bidirectional"))
      (node (ref "B6") (pin "P5") (pinfunction "P5_P5") (pintype "bidirectional"))
      (node (ref "R5") (pin "1") (pinfunction "1_1") (pintype "passive"))
      (node (ref "U$21") (pin "7") (pinfunction "SD1_7") (pintype "bidirectional"))
    )
    (net (code "68") (name "SDA") (class "Default")
      (node (ref "U$1") (pin "P3") (pinfunction "8_P3") (pintype "bidirectional"))
      (node (ref "U$21") (pin "2") (pinfunction "SDA_2") (pintype "bidirectional"))
    )
    (net (code "69") (name "SDO") (class "Default")
      (node (ref "R20") (pin "2") (pinfunction "2_2") (pintype "passive"))
      (node (ref "U$1") (pin "P8") (pinfunction "15_P8") (pintype "bidirectional"))
      (node (ref "U$7") (pin "P14") (pinfunction "DS_P14") (pintype "bidirectional"))
    )
    (net (code "70") (name "SHCP") (class "Default")
      (node (ref "R13") (pin "2") (pinfunction "2_2") (pintype "passive"))
      (node (ref "U$1") (pin "P18") (pinfunction "5_P18") (pintype "bidirectional"))
      (node (ref "U$22") (pin "P11") (pinfunction "SHCP_P11") (pintype "bidirectional"))
      (node (ref "U$23") (pin "P11") (pinfunction "SHCP_P11") (pintype "bidirectional"))
      (node (ref "U$24") (pin "P11") (pinfunction "SHCP_P11") (pintype "bidirectional"))
      (node (ref "U$25") (pin "P11") (pinfunction "SHCP_P11") (pintype "bidirectional"))
      (node (ref "U$26") (pin "P11") (pinfunction "SHCP_P11") (pintype "bidirectional"))
      (node (ref "U$7") (pin "P11") (pinfunction "SHCP_P11") (pintype "bidirectional"))
    )
    (net (code "71") (name "STCP") (class "Default")
      (node (ref "R14") (pin "2") (pinfunction "2_2") (pintype "passive"))
      (node (ref "U$1") (pin "P16") (pinfunction "4_P16") (pintype "bidirectional"))
      (node (ref "U$22") (pin "P12") (pinfunction "STCP_P12") (pintype "bidirectional"))
      (node (ref "U$23") (pin "P12") (pinfunction "STCP_P12") (pintype "bidirectional"))
      (node (ref "U$24") (pin "P12") (pinfunction "STCP_P12") (pintype "bidirectional"))
      (node (ref "U$25") (pin "P12") (pinfunction "STCP_P12") (pintype "bidirectional"))
      (node (ref "U$26") (pin "P12") (pinfunction "STCP_P12") (pintype "bidirectional"))
      (node (ref "U$7") (pin "P12") (pinfunction "STCP_P12") (pintype "bidirectional"))
    )
    (net (code "72") (name "unconnected-(U$1-1-PadP12)") (class "Default")
      (node (ref "U$1") (pin "P12") (pinfunction "1_P12") (pintype "bidirectional"))
    )
    (net (code "73") (name "unconnected-(U$1-3V3-PadP1)") (class "Default")
      (node (ref "U$1") (pin "P1") (pinfunction "3V3_P1") (pintype "bidirectional"))
    )
    (net (code "74") (name "unconnected-(U$1-6-PadP22)") (class "Default")
      (node (ref "U$1") (pin "P22") (pinfunction "6_P22") (pintype "bidirectional"))
    )
    (net (code "75") (name "unconnected-(U$1-7-PadP7)") (class "Default")
      (node (ref "U$1") (pin "P7") (pinfunction "7_P7") (pintype "bidirectional"))
    )
    (net (code "76") (name "unconnected-(U$1-11-PadP26)") (class "Default")
      (node (ref "U$1") (pin "P26") (pinfunction "11_P26") (pintype "bidirectional"))
    )
    (net (code "77") (name "unconnected-(U$1-16-PadP10)") (class "Default")
      (node (ref "U$1") (pin "P10") (pinfunction "16_P10") (pintype "bidirectional"))
    )
    (net (code "78") (name "unconnected-(U$1-22-PadP31)") (class "Default")
      (node (ref "U$1") (pin "P31") (pinfunction "22_P31") (pintype "bidirectional"))
    )
    (net (code "79") (name "unconnected-(U$1-23-PadP33)") (class "Default")
      (node (ref "U$1") (pin "P33") (pinfunction "23_P33") (pintype "bidirectional"))
    )
    (net (code "80") (name "unconnected-(U$1-24-PadP35)") (class "Default")
      (node (ref "U$1") (pin "P35") (pinfunction "24_P35") (pintype "bidirectional"))
    )
    (net (code "81") (name "unconnected-(U$1-25-PadP37)") (class "Default")
      (node (ref "U$1") (pin "P37") (pinfunction "25_P37") (pintype "bidirectional"))
    )
    (net (code "82") (name "unconnected-(U$1-26-PadP32)") (class "Default")
      (node (ref "U$1") (pin "P32") (pinfunction "26_P32") (pintype "bidirectional"))
    )
    (net (code "83") (name "unconnected-(U$1-27-PadP36)") (class "Default")
      (node (ref "U$1") (pin "P36") (pinfunction "27_P36") (pintype "bidirectional"))
    )
    (net (code "84") (name "unconnected-(U$1-28-PadP38)") (class "Default")
      (node (ref "U$1") (pin "P38") (pinfunction "28_P38") (pintype "bidirectional"))
    )
    (net (code "85") (name "unconnected-(U$1-29-PadP40)") (class "Default")
      (node (ref "U$1") (pin "P40") (pinfunction "29_P40") (pintype "bidirectional"))
    )
    (net (code "86") (name "unconnected-(U$1-30-PadP27)") (class "Default")
      (node (ref "U$1") (pin "P27") (pinfunction "30_P27") (pintype "bidirectional"))
    )
    (net (code "87") (name "unconnected-(U$1-31-PadP28)") (class "Default")
      (node (ref "U$1") (pin "P28") (pinfunction "31_P28") (pintype "bidirectional"))
    )
    (net (code "88") (name "unconnected-(U$7-Q0-PadP15)") (class "Default")
      (node (ref "U$7") (pin "P15") (pinfunction "Q0_P15") (pintype "bidirectional"))
    )
    (net (code "89") (name "unconnected-(U$7-Q1-PadP1)") (class "Default")
      (node (ref "U$7") (pin "P1") (pinfunction "Q1_P1") (pintype "bidirectional"))
    )
    (net (code "90") (name "unconnected-(U$7-Q2-PadP2)") (class "Default")
      (node (ref "U$7") (pin "P2") (pinfunction "Q2_P2") (pintype "bidirectional"))
    )
    (net (code "91") (name "unconnected-(U$7-Q3-PadP3)") (class "Default")
      (node (ref "U$7") (pin "P3") (pinfunction "Q3_P3") (pintype "bidirectional"))
    )
    (net (code "92") (name "unconnected-(U$22-Q0-PadP15)") (class "Default")
      (node (ref "U$22") (pin "P15") (pinfunction "Q0_P15") (pintype "bidirectional"))
    )
    (net (code "93") (name "unconnected-(U$22-Q1-PadP1)") (class "Default")
      (node (ref "U$22") (pin "P1") (pinfunction "Q1_P1") (pintype "bidirectional"))
    )
    (net (code "94") (name "unconnected-(U$22-Q2-PadP2)") (class "Default")
      (node (ref "U$22") (pin "P2") (pinfunction "Q2_P2") (pintype "bidirectional"))
    )
    (net (code "95") (name "unconnected-(U$22-Q3-PadP3)") (class "Default")
      (node (ref "U$22") (pin "P3") (pinfunction "Q3_P3") (pintype "bidirectional"))
    )
    (net (code "96") (name "unconnected-(U$23-Q0-PadP15)") (class "Default")
      (node (ref "U$23") (pin "P15") (pinfunction "Q0_P15") (pintype "bidirectional"))
    )
    (net (code "97") (name "unconnected-(U$23-Q1-PadP1)") (class "Default")
      (node (ref "U$23") (pin "P1") (pinfunction "Q1_P1") (pintype "bidirectional"))
    )
    (net (code "98") (name "unconnected-(U$23-Q2-PadP2)") (class "Default")
      (node (ref "U$23") (pin "P2") (pinfunction "Q2_P2") (pintype "bidirectional"))
    )
    (net (code "99") (name "unconnected-(U$23-Q3-PadP3)") (class "Default")
      (node (ref "U$23") (pin "P3") (pinfunction "Q3_P3") (pintype "bidirectional"))
    )
    (net (code "100") (name "unconnected-(U$24-Q0-PadP15)") (class "Default")
      (node (ref "U$24") (pin "P15") (pinfunction "Q0_P15") (pintype "bidirectional"))
    )
    (net (code "101") (name "unconnected-(U$24-Q1-PadP1)") (class "Default")
      (node (ref "U$24") (pin "P1") (pinfunction "Q1_P1") (pintype "bidirectional"))
    )
    (net (code "102") (name "unconnected-(U$24-Q2-PadP2)") (class "Default")
      (node (ref "U$24") (pin "P2") (pinfunction "Q2_P2") (pintype "bidirectional"))
    )
    (net (code "103") (name "unconnected-(U$24-Q3-PadP3)") (class "Default")
      (node (ref "U$24") (pin "P3") (pinfunction "Q3_P3") (pintype "bidirectional"))
    )
    (net (code "104") (name "unconnected-(U$25-Q0-PadP15)") (class "Default")
      (node (ref "U$25") (pin "P15") (pinfunction "Q0_P15") (pintype "bidirectional"))
    )
    (net (code "105") (name "unconnected-(U$25-Q1-PadP1)") (class "Default")
      (node (ref "U$25") (pin "P1") (pinfunction "Q1_P1") (pintype "bidirectional"))
    )
    (net (code "106") (name "unconnected-(U$25-Q2-PadP2)") (class "Default")
      (node (ref "U$25") (pin "P2") (pinfunction "Q2_P2") (pintype "bidirectional"))
    )
    (net (code "107") (name "unconnected-(U$25-Q3-PadP3)") (class "Default")
      (node (ref "U$25") (pin "P3") (pinfunction "Q3_P3") (pintype "bidirectional"))
    )
    (net (code "108") (name "unconnected-(U$26-Q0-PadP15)") (class "Default")
      (node (ref "U$26") (pin "P15") (pinfunction "Q0_P15") (pintype "bidirectional"))
    )
    (net (code "109") (name "unconnected-(U$26-Q1-PadP1)") (class "Default")
      (node (ref "U$26") (pin "P1") (pinfunction "Q1_P1") (pintype "bidirectional"))
    )
    (net (code "110") (name "unconnected-(U$26-Q2-PadP2)") (class "Default")
      (node (ref "U$26") (pin "P2") (pinfunction "Q2_P2") (pintype "bidirectional"))
    )
    (net (code "111") (name "unconnected-(U$26-Q3-PadP3)") (class "Default")
      (node (ref "U$26") (pin "P3") (pinfunction "Q3_P3") (pintype "bidirectional"))
    )
    (net (code "112") (name "unconnected-(U$26-Q7S-PadP9)") (class "Default")
      (node (ref "U$26") (pin "P9") (pinfunction "Q7S_P9") (pintype "bidirectional"))
    )
  )
)
